# pe43711.net
KiCad netlist of a schematic drawn in EasyEDA Pro
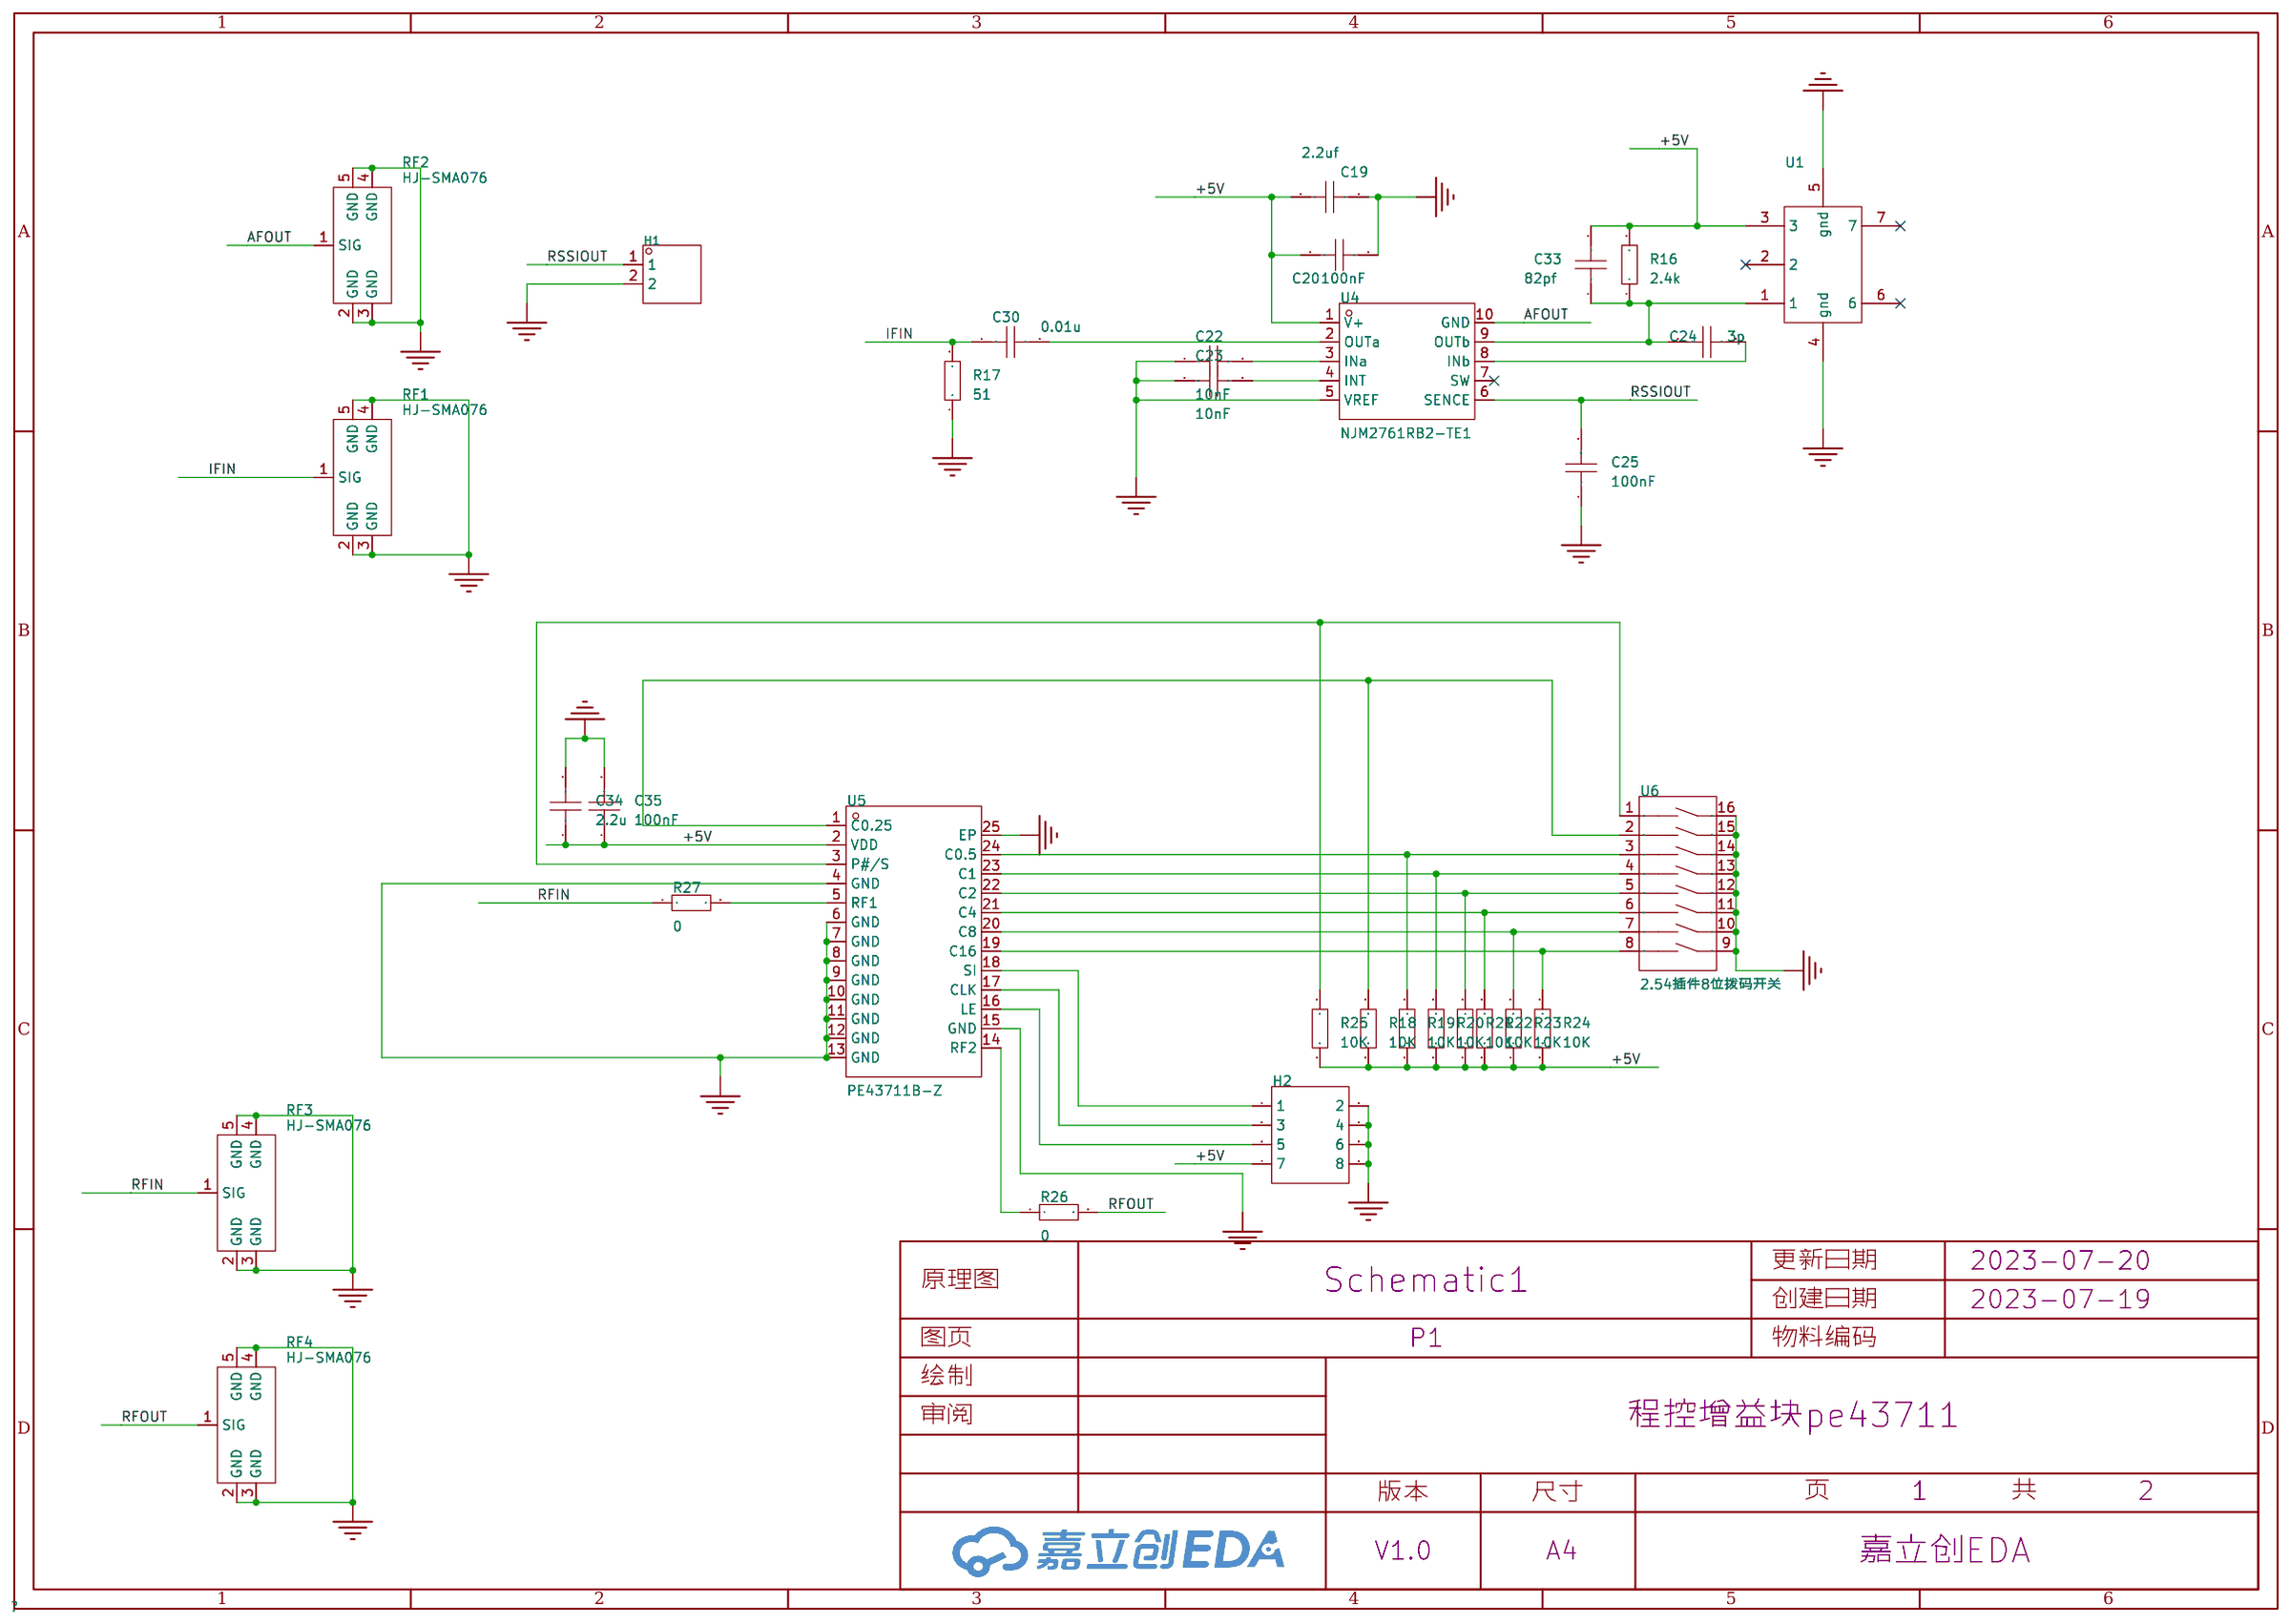
[diagram p0: P1]
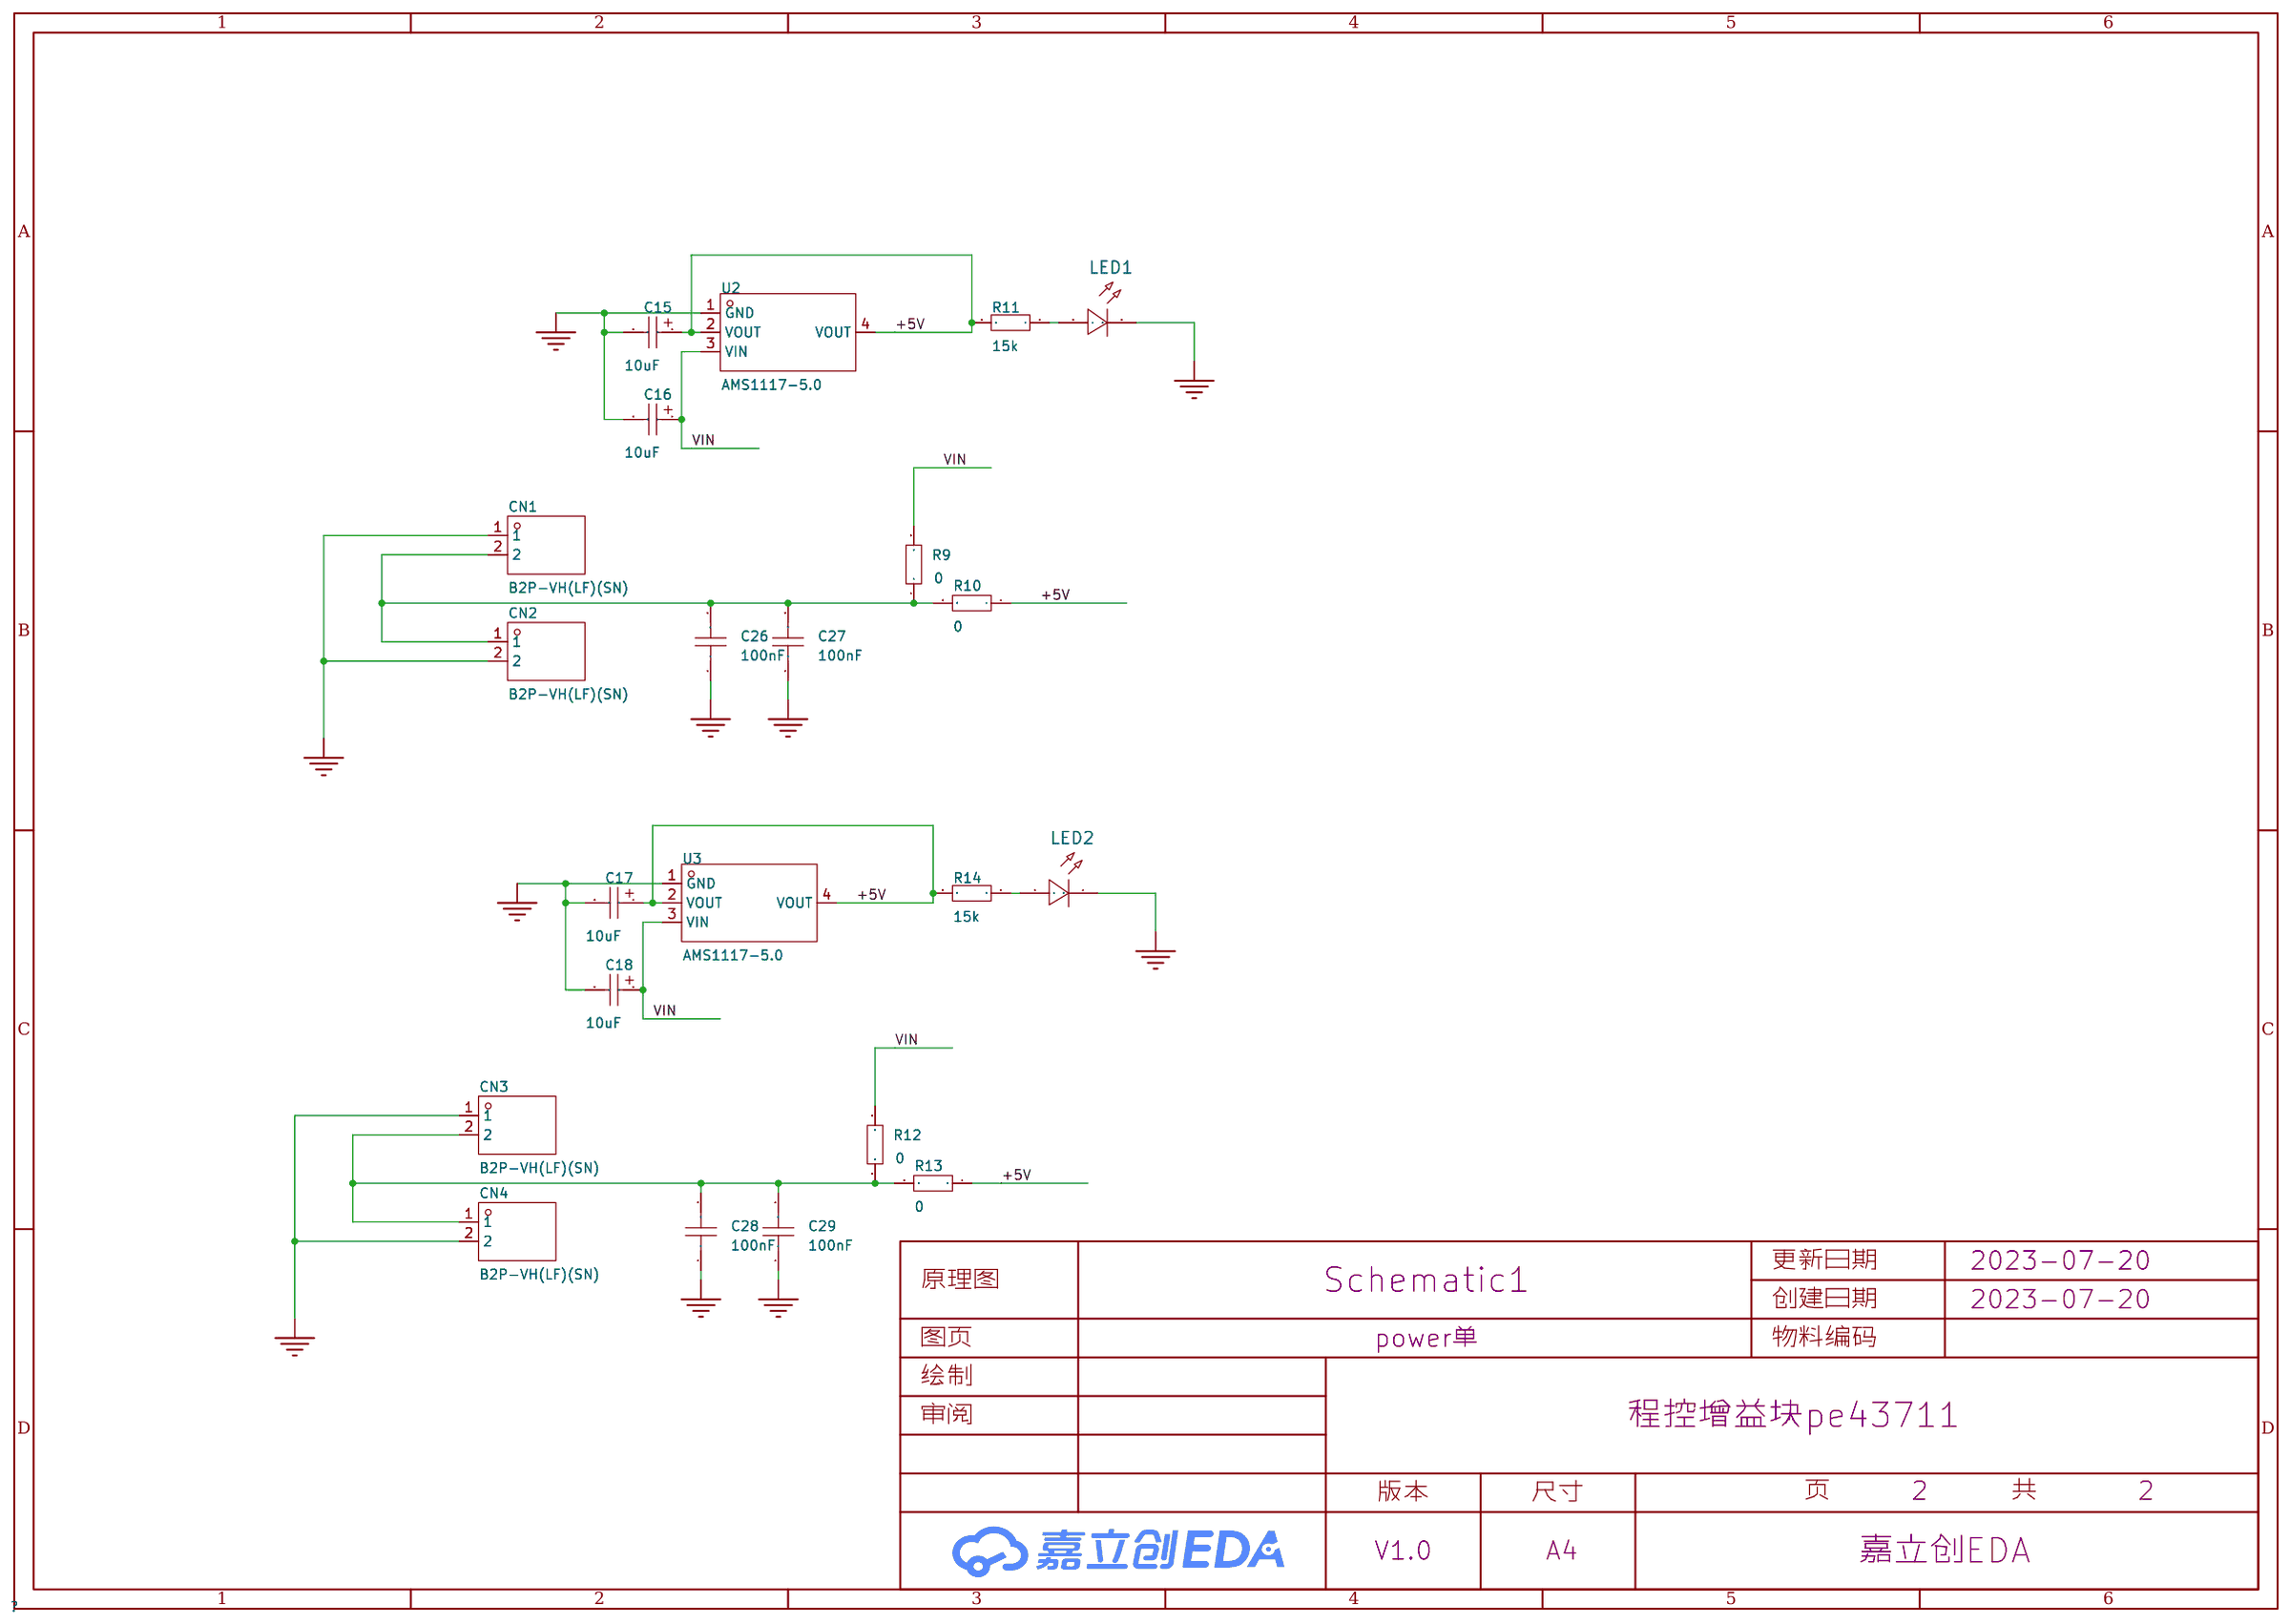
[diagram p1: power单]

(export (version "E")
  (design (tool "Eeschema 10.0.6"))
  (components
    (comp (ref "C19")
      (value "2.2uf")
      (footprint "easyedapro:C0603")
      (libsource (lib "easyedapro") (part "CapAcitance"))
    )
    (comp (ref "C20")
      (value "100nF")
      (footprint "easyedapro:C0603")
      (libsource (lib "easyedapro") (part "CapAcitance"))
    )
    (comp (ref "C22")
      (value "10nF")
      (footprint "easyedapro:C0603")
      (libsource (lib "easyedapro") (part "CapAcitance"))
    )
    (comp (ref "C23")
      (value "10nF")
      (footprint "easyedapro:C0603")
      (libsource (lib "easyedapro") (part "CapAcitance"))
    )
    (comp (ref "C24")
      (value "3p")
      (footprint "easyedapro:C0603")
      (libsource (lib "easyedapro") (part "CapAcitance"))
    )
    (comp (ref "C25")
      (value "100nF")
      (footprint "easyedapro:C0603")
      (libsource (lib "easyedapro") (part "CapAcitance"))
    )
    (comp (ref "C30")
      (value "0.01u")
      (footprint "easyedapro:C0603")
      (libsource (lib "easyedapro") (part "CapAcitance"))
    )
    (comp (ref "C33")
      (value "82pf")
      (footprint "easyedapro:C0603")
      (libsource (lib "easyedapro") (part "CapAcitance"))
    )
    (comp (ref "C34")
      (value "2.2u")
      (footprint "easyedapro:C0603")
      (libsource (lib "easyedapro") (part "CapAcitance"))
    )
    (comp (ref "C35")
      (value "100nF")
      (footprint "easyedapro:C0603")
      (libsource (lib "easyedapro") (part "CapAcitance"))
    )
    (comp (ref "H1")
      (value "~")
      (footprint "easyedapro:HDR-TH_2P-P2.54-V-M-1")
      (libsource (lib "easyedapro") (part "210S-1*2P L=11.6MMGold-plated black"))
    )
    (comp (ref "H2")
      (value "~")
      (footprint "easyedapro:HDR-TH_8P-P2.54-V-F-R2-C4-S2.54-1")
      (libsource (lib "easyedapro") (part "HDR-F-2.54_2x4"))
    )
    (comp (ref "R16")
      (value "2.4k")
      (footprint "easyedapro:R0603")
      (libsource (lib "easyedapro") (part "电阻"))
    )
    (comp (ref "R17") (value "51") (footprint "easyedapro:R0603") (libsource (lib "easyedapro") (part "电阻")))
    (comp (ref "R18") (value "10K") (footprint "easyedapro:R0603") (libsource (lib "easyedapro") (part "电阻")))
    (comp (ref "R19") (value "10K") (footprint "easyedapro:R0603") (libsource (lib "easyedapro") (part "电阻")))
    (comp (ref "R20") (value "10K") (footprint "easyedapro:R0603") (libsource (lib "easyedapro") (part "电阻")))
    (comp (ref "R21") (value "10K") (footprint "easyedapro:R0603") (libsource (lib "easyedapro") (part "电阻")))
    (comp (ref "R22") (value "10K") (footprint "easyedapro:R0603") (libsource (lib "easyedapro") (part "电阻")))
    (comp (ref "R23") (value "10K") (footprint "easyedapro:R0603") (libsource (lib "easyedapro") (part "电阻")))
    (comp (ref "R24") (value "10K") (footprint "easyedapro:R0603") (libsource (lib "easyedapro") (part "电阻")))
    (comp (ref "R25") (value "10K") (footprint "easyedapro:R0603") (libsource (lib "easyedapro") (part "电阻")))
    (comp (ref "R26") (value "0") (footprint "easyedapro:R0603") (libsource (lib "easyedapro") (part "电阻")))
    (comp (ref "R27") (value "0") (footprint "easyedapro:R0603") (libsource (lib "easyedapro") (part "电阻")))
    (comp (ref "RF1")
      (value "HJ-SMA076")
      (footprint "easyedapro:SMA-SMD_HJ-SMA076")
      (description "连接器类型:板端;射频系列:SMA;接口类型:内孔;端口数量:1;阻抗:-;频率-最大值:-;样式:偏脚;接口直径:-;接口长度/高度:-;工作温度范围:-;")
      (fields (field (name "Manufacturer") "皇捷"))
      (libsource (lib "easyedapro") (part "HJ-SMA076"))
    )
    (comp (ref "RF2")
      (value "HJ-SMA076")
      (footprint "easyedapro:SMA-SMD_HJ-SMA076")
      (description "连接器类型:板端;射频系列:SMA;接口类型:内孔;端口数量:1;阻抗:-;频率-最大值:-;样式:偏脚;接口直径:-;接口长度/高度:-;工作温度范围:-;")
      (fields (field (name "Manufacturer") "皇捷"))
      (libsource (lib "easyedapro") (part "HJ-SMA076"))
    )
    (comp (ref "RF3")
      (value "HJ-SMA076")
      (footprint "easyedapro:SMA-SMD_HJ-SMA076")
      (description "连接器类型:板端;射频系列:SMA;接口类型:内孔;端口数量:1;阻抗:-;频率-最大值:-;样式:偏脚;接口直径:-;接口长度/高度:-;工作温度范围:-;")
      (fields (field (name "Manufacturer") "皇捷"))
      (libsource (lib "easyedapro") (part "HJ-SMA076"))
    )
    (comp (ref "RF4")
      (value "HJ-SMA076")
      (footprint "easyedapro:SMA-SMD_HJ-SMA076")
      (description "连接器类型:板端;射频系列:SMA;接口类型:内孔;端口数量:1;阻抗:-;频率-最大值:-;样式:偏脚;接口直径:-;接口长度/高度:-;工作温度范围:-;")
      (fields (field (name "Manufacturer") "皇捷"))
      (libsource (lib "easyedapro") (part "HJ-SMA076"))
    )
    (comp (ref "U1") (value "~") (footprint "easyedapro:中周") (libsource (lib "easyedapro") (part "中周")))
    (comp (ref "U4")
      (value "NJM2761RB2-TE1")
      (footprint "easyedapro:MSOP-10_L2.9-W2.8-P0.50-LS4.0-BL")
      (fields (field (name "Manufacturer") "JRC"))
      (libsource (lib "easyedapro") (part "NJM2761RB2-TE1"))
    )
    (comp (ref "U5")
      (value "PE43711B-Z")
      (footprint "easyedapro:VQFN-24_L4.0-W4.0-P0.50-BL-EP2.3")
      (description "衰减值:0dB~31.75dB;频率范围:9kHz~6GHz;阻抗:50Ω;")
      (fields (field (name "Manufacturer") "PSemi"))
      (libsource (lib "easyedapro") (part "PE43711B-Z"))
    )
    (comp (ref "U6")
      (value "2.54插件8位拨码开关")
      (footprint "easyedapro:SW-TH_16P-L21.9-W9.9-P2.54-LS7.8")
      (libsource (lib "easyedapro") (part "2.54插件8位拨码开关"))
    )
    (comp (ref "C15")
      (value "10uF")
      (footprint "easyedapro:CAP-SMD_L3.2-W1.6-RD-C7171")
      (description "容值:10uF;精度:±10%;额定电压:16V;等效串联电阻:3Ω@100kHz;")
      (fields (field (name "Manufacturer Part") "TAJA106K016RNJ") (field (name "Manufacturer") "Kyocera AVX"))
      (libsource (lib "easyedapro") (part "TAJA106K016RNJ"))
    )
    (comp (ref "C16")
      (value "10uF")
      (footprint "easyedapro:CAP-SMD_L3.2-W1.6-RD-C7171")
      (description "容值:10uF;精度:±10%;额定电压:16V;等效串联电阻:3Ω@100kHz;")
      (fields (field (name "Manufacturer Part") "TAJA106K016RNJ") (field (name "Manufacturer") "Kyocera AVX"))
      (libsource (lib "easyedapro") (part "TAJA106K016RNJ"))
    )
    (comp (ref "C17")
      (value "10uF")
      (footprint "easyedapro:CAP-SMD_L3.2-W1.6-RD-C7171")
      (description "容值:10uF;精度:±10%;额定电压:16V;等效串联电阻:3Ω@100kHz;")
      (fields (field (name "Manufacturer Part") "TAJA106K016RNJ") (field (name "Manufacturer") "Kyocera AVX"))
      (libsource (lib "easyedapro") (part "TAJA106K016RNJ"))
    )
    (comp (ref "C18")
      (value "10uF")
      (footprint "easyedapro:CAP-SMD_L3.2-W1.6-RD-C7171")
      (description "容值:10uF;精度:±10%;额定电压:16V;等效串联电阻:3Ω@100kHz;")
      (fields (field (name "Manufacturer Part") "TAJA106K016RNJ") (field (name "Manufacturer") "Kyocera AVX"))
      (libsource (lib "easyedapro") (part "TAJA106K016RNJ"))
    )
    (comp (ref "C26")
      (value "100nF")
      (footprint "easyedapro:C0603")
      (libsource (lib "easyedapro") (part "CapAcitance"))
    )
    (comp (ref "C27")
      (value "100nF")
      (footprint "easyedapro:C0603")
      (libsource (lib "easyedapro") (part "CapAcitance"))
    )
    (comp (ref "C28")
      (value "100nF")
      (footprint "easyedapro:C0603")
      (libsource (lib "easyedapro") (part "CapAcitance"))
    )
    (comp (ref "C29")
      (value "100nF")
      (footprint "easyedapro:C0603")
      (libsource (lib "easyedapro") (part "CapAcitance"))
    )
    (comp (ref "CN1")
      (value "B2P-VH(LF)(SN)")
      (footprint "easyedapro:CONN-TH_B2P-VH-LF-SN")
      (description "参考系列:VH;间距:3.96mm;插针结构:1x2P;排数:1;每排PIN数:2;行距:-;安装方式:-;触头材质:黄铜;")
      (fields (field (name "Manufacturer") "JST"))
      (libsource (lib "easyedapro") (part "B2P-VH (LF)(SN)"))
    )
    (comp (ref "CN2")
      (value "B2P-VH(LF)(SN)")
      (footprint "easyedapro:CONN-TH_B2P-VH-LF-SN")
      (description "参考系列:VH;间距:3.96mm;插针结构:1x2P;排数:1;每排PIN数:2;行距:-;安装方式:-;触头材质:黄铜;")
      (fields (field (name "Manufacturer") "JST"))
      (libsource (lib "easyedapro") (part "B2P-VH (LF)(SN)"))
    )
    (comp (ref "CN3")
      (value "B2P-VH(LF)(SN)")
      (footprint "easyedapro:CONN-TH_B2P-VH-LF-SN")
      (description "参考系列:VH;间距:3.96mm;插针结构:1x2P;排数:1;每排PIN数:2;行距:-;安装方式:-;触头材质:黄铜;")
      (fields (field (name "Manufacturer") "JST"))
      (libsource (lib "easyedapro") (part "B2P-VH (LF)(SN)"))
    )
    (comp (ref "CN4")
      (value "B2P-VH(LF)(SN)")
      (footprint "easyedapro:CONN-TH_B2P-VH-LF-SN")
      (description "参考系列:VH;间距:3.96mm;插针结构:1x2P;排数:1;每排PIN数:2;行距:-;安装方式:-;触头材质:黄铜;")
      (fields (field (name "Manufacturer") "JST"))
      (libsource (lib "easyedapro") (part "B2P-VH (LF)(SN)"))
    )
    (comp (ref "LED1")
      (value "~")
      (footprint "easyedapro:LED_0603")
      (libsource (lib "easyedapro") (part "LED_R"))
    )
    (comp (ref "LED2")
      (value "~")
      (footprint "easyedapro:LED_0603")
      (libsource (lib "easyedapro") (part "LED_R"))
    )
    (comp (ref "R9") (value "0") (footprint "easyedapro:R0603") (libsource (lib "easyedapro") (part "电阻")))
    (comp (ref "R10") (value "0") (footprint "easyedapro:R0603") (libsource (lib "easyedapro") (part "电阻")))
    (comp (ref "R11") (value "15k") (footprint "easyedapro:R0603") (libsource (lib "easyedapro") (part "电阻")))
    (comp (ref "R12") (value "0") (footprint "easyedapro:R0603") (libsource (lib "easyedapro") (part "电阻")))
    (comp (ref "R13") (value "0") (footprint "easyedapro:R0603") (libsource (lib "easyedapro") (part "电阻")))
    (comp (ref "R14") (value "15k") (footprint "easyedapro:R0603") (libsource (lib "easyedapro") (part "电阻")))
    (comp (ref "U2")
      (value "AMS1117-5.0")
      (footprint "easyedapro:SOT-223_L6.5-W3.5-P2.30-LS7.0-BR")
      (description "输出类型:固定;输出极性:正;最大输入电压:15V;输出电压:5V;输出电流:1A;电源纹波抑制比(PSRR):68dB@(120Hz);")
      (fields (field (name "Manufacturer") "AMS"))
      (libsource (lib "easyedapro") (part "AMS1117-5.0"))
    )
    (comp (ref "U3")
      (value "AMS1117-5.0")
      (footprint "easyedapro:SOT-223_L6.5-W3.5-P2.30-LS7.0-BR")
      (description "输出类型:固定;输出极性:正;最大输入电压:15V;输出电压:5V;输出电流:1A;电源纹波抑制比(PSRR):68dB@(120Hz);")
      (fields (field (name "Manufacturer") "AMS"))
      (libsource (lib "easyedapro") (part "AMS1117-5.0"))
    )
  )
  (nets
    (net (code "1") (name "+5V") (class "Default")
      (node (ref "C15") (pin "1") (pinfunction "1_1") (pintype "input"))
      (node (ref "C17") (pin "1") (pinfunction "1_1") (pintype "input"))
      (node (ref "C19") (pin "1") (pinfunction "1_1") (pintype "input"))
      (node (ref "C20") (pin "1") (pinfunction "1_1") (pintype "input"))
      (node (ref "C33") (pin "2") (pinfunction "2_2") (pintype "input"))
      (node (ref "C34") (pin "1") (pinfunction "1_1") (pintype "input"))
      (node (ref "C35") (pin "1") (pinfunction "1_1") (pintype "input"))
      (node (ref "H2") (pin "7") (pinfunction "7_7") (pintype "input"))
      (node (ref "R10") (pin "1") (pinfunction "1_1") (pintype "input"))
      (node (ref "R11") (pin "2") (pinfunction "2_2") (pintype "input"))
      (node (ref "R13") (pin "1") (pinfunction "1_1") (pintype "input"))
      (node (ref "R14") (pin "2") (pinfunction "2_2") (pintype "input"))
      (node (ref "R16") (pin "2") (pinfunction "2_2") (pintype "input"))
      (node (ref "R18") (pin "1") (pinfunction "1_1") (pintype "input"))
      (node (ref "R19") (pin "1") (pinfunction "1_1") (pintype "input"))
      (node (ref "R20") (pin "1") (pinfunction "1_1") (pintype "input"))
      (node (ref "R21") (pin "1") (pinfunction "1_1") (pintype "input"))
      (node (ref "R22") (pin "1") (pinfunction "1_1") (pintype "input"))
      (node (ref "R23") (pin "1") (pinfunction "1_1") (pintype "input"))
      (node (ref "R24") (pin "1") (pinfunction "1_1") (pintype "input"))
      (node (ref "R25") (pin "1") (pinfunction "1_1") (pintype "input"))
      (node (ref "U1") (pin "3") (pinfunction "3_3") (pintype "input"))
      (node (ref "U2") (pin "2") (pinfunction "VOUT_2") (pintype "input"))
      (node (ref "U2") (pin "4") (pinfunction "VOUT_4") (pintype "input"))
      (node (ref "U3") (pin "2") (pinfunction "VOUT_2") (pintype "input"))
      (node (ref "U3") (pin "4") (pinfunction "VOUT_4") (pintype "input"))
      (node (ref "U4") (pin "1") (pinfunction "V+_1") (pintype "input"))
      (node (ref "U5") (pin "2") (pinfunction "VDD_2") (pintype "input"))
    )
    (net (code "2") (name "AFOUT") (class "Default")
      (node (ref "RF2") (pin "1") (pinfunction "SIG_1") (pintype "input"))
      (node (ref "U4") (pin "10") (pinfunction "GND_10") (pintype "input"))
    )
    (net (code "3") (name "GND") (class "Default")
      (node (ref "C15") (pin "2") (pinfunction "2_2") (pintype "input"))
      (node (ref "C16") (pin "2") (pinfunction "2_2") (pintype "input"))
      (node (ref "C17") (pin "2") (pinfunction "2_2") (pintype "input"))
      (node (ref "C18") (pin "2") (pinfunction "2_2") (pintype "input"))
      (node (ref "C19") (pin "2") (pinfunction "2_2") (pintype "input"))
      (node (ref "C20") (pin "2") (pinfunction "2_2") (pintype "input"))
      (node (ref "C22") (pin "1") (pinfunction "1_1") (pintype "input"))
      (node (ref "C23") (pin "1") (pinfunction "1_1") (pintype "input"))
      (node (ref "C25") (pin "1") (pinfunction "1_1") (pintype "input"))
      (node (ref "C26") (pin "1") (pinfunction "1_1") (pintype "input"))
      (node (ref "C27") (pin "1") (pinfunction "1_1") (pintype "input"))
      (node (ref "C28") (pin "1") (pinfunction "1_1") (pintype "input"))
      (node (ref "C29") (pin "1") (pinfunction "1_1") (pintype "input"))
      (node (ref "C34") (pin "2") (pinfunction "2_2") (pintype "input"))
      (node (ref "C35") (pin "2") (pinfunction "2_2") (pintype "input"))
      (node (ref "CN1") (pin "1") (pinfunction "1_1") (pintype "input"))
      (node (ref "CN2") (pin "2") (pinfunction "2_2") (pintype "input"))
      (node (ref "CN3") (pin "1") (pinfunction "1_1") (pintype "input"))
      (node (ref "CN4") (pin "2") (pinfunction "2_2") (pintype "input"))
      (node (ref "H1") (pin "2") (pinfunction "2_2") (pintype "input"))
      (node (ref "H2") (pin "2") (pinfunction "2_2") (pintype "input"))
      (node (ref "H2") (pin "4") (pinfunction "4_4") (pintype "input"))
      (node (ref "H2") (pin "6") (pinfunction "6_6") (pintype "input"))
      (node (ref "H2") (pin "8") (pinfunction "8_8") (pintype "input"))
      (node (ref "LED1") (pin "1") (pinfunction "C_1") (pintype "input"))
      (node (ref "LED2") (pin "1") (pinfunction "C_1") (pintype "input"))
      (node (ref "R17") (pin "1") (pinfunction "1_1") (pintype "input"))
      (node (ref "RF1") (pin "2") (pinfunction "GND_2") (pintype "input"))
      (node (ref "RF1") (pin "3") (pinfunction "GND_3") (pintype "input"))
      (node (ref "RF1") (pin "4") (pinfunction "GND_4") (pintype "input"))
      (node (ref "RF1") (pin "5") (pinfunction "GND_5") (pintype "input"))
      (node (ref "RF2") (pin "2") (pinfunction "GND_2") (pintype "input"))
      (node (ref "RF2") (pin "3") (pinfunction "GND_3") (pintype "input"))
      (node (ref "RF2") (pin "4") (pinfunction "GND_4") (pintype "input"))
      (node (ref "RF2") (pin "5") (pinfunction "GND_5") (pintype "input"))
      (node (ref "RF3") (pin "2") (pinfunction "GND_2") (pintype "input"))
      (node (ref "RF3") (pin "3") (pinfunction "GND_3") (pintype "input"))
      (node (ref "RF3") (pin "4") (pinfunction "GND_4") (pintype "input"))
      (node (ref "RF3") (pin "5") (pinfunction "GND_5") (pintype "input"))
      (node (ref "RF4") (pin "2") (pinfunction "GND_2") (pintype "input"))
      (node (ref "RF4") (pin "3") (pinfunction "GND_3") (pintype "input"))
      (node (ref "RF4") (pin "4") (pinfunction "GND_4") (pintype "input"))
      (node (ref "RF4") (pin "5") (pinfunction "GND_5") (pintype "input"))
      (node (ref "U1") (pin "4") (pinfunction "gnd_4") (pintype "input"))
      (node (ref "U1") (pin "5") (pinfunction "gnd_5") (pintype "input"))
      (node (ref "U2") (pin "1") (pinfunction "GND_1") (pintype "input"))
      (node (ref "U3") (pin "1") (pinfunction "GND_1") (pintype "input"))
      (node (ref "U4") (pin "5") (pinfunction "VREF_5") (pintype "input"))
      (node (ref "U5") (pin "10") (pinfunction "GND_10") (pintype "input"))
      (node (ref "U5") (pin "11") (pinfunction "GND_11") (pintype "input"))
      (node (ref "U5") (pin "12") (pinfunction "GND_12") (pintype "input"))
      (node (ref "U5") (pin "13") (pinfunction "GND_13") (pintype "input"))
      (node (ref "U5") (pin "15") (pinfunction "GND_15") (pintype "input"))
      (node (ref "U5") (pin "25") (pinfunction "EP_25") (pintype "input"))
      (node (ref "U5") (pin "4") (pinfunction "GND_4") (pintype "input"))
      (node (ref "U5") (pin "6") (pinfunction "GND_6") (pintype "input"))
      (node (ref "U5") (pin "7") (pinfunction "GND_7") (pintype "input"))
      (node (ref "U5") (pin "8") (pinfunction "GND_8") (pintype "input"))
      (node (ref "U5") (pin "9") (pinfunction "GND_9") (pintype "input"))
      (node (ref "U6") (pin "10") (pinfunction "10_10") (pintype "input"))
      (node (ref "U6") (pin "11") (pinfunction "11_11") (pintype "input"))
      (node (ref "U6") (pin "12") (pinfunction "12_12") (pintype "input"))
      (node (ref "U6") (pin "13") (pinfunction "13_13") (pintype "input"))
      (node (ref "U6") (pin "14") (pinfunction "14_14") (pintype "input"))
      (node (ref "U6") (pin "15") (pinfunction "15_15") (pintype "input"))
      (node (ref "U6") (pin "16") (pinfunction "16_16") (pintype "input"))
      (node (ref "U6") (pin "9") (pinfunction "9_9") (pintype "input"))
    )
    (net (code "4") (name "IFIN") (class "Default")
      (node (ref "C30") (pin "1") (pinfunction "1_1") (pintype "input"))
      (node (ref "R17") (pin "2") (pinfunction "2_2") (pintype "input"))
      (node (ref "RF1") (pin "1") (pinfunction "SIG_1") (pintype "input"))
    )
    (net (code "5") (name "Net-(C26-Pad2)") (class "Default")
      (node (ref "C26") (pin "2") (pinfunction "2_2") (pintype "input"))
      (node (ref "C27") (pin "2") (pinfunction "2_2") (pintype "input"))
      (node (ref "CN1") (pin "2") (pinfunction "2_2") (pintype "input"))
      (node (ref "CN2") (pin "1") (pinfunction "1_1") (pintype "input"))
      (node (ref "R10") (pin "2") (pinfunction "2_2") (pintype "input"))
      (node (ref "R9") (pin "1") (pinfunction "1_1") (pintype "input"))
    )
    (net (code "6") (name "Net-(C28-Pad2)") (class "Default")
      (node (ref "C28") (pin "2") (pinfunction "2_2") (pintype "input"))
      (node (ref "C29") (pin "2") (pinfunction "2_2") (pintype "input"))
      (node (ref "CN3") (pin "2") (pinfunction "2_2") (pintype "input"))
      (node (ref "CN4") (pin "1") (pinfunction "1_1") (pintype "input"))
      (node (ref "R12") (pin "1") (pinfunction "1_1") (pintype "input"))
      (node (ref "R13") (pin "2") (pinfunction "2_2") (pintype "input"))
    )
    (net (code "7") (name "Net-(LED1-A)") (class "Default")
      (node (ref "LED1") (pin "2") (pinfunction "A_2") (pintype "input"))
      (node (ref "R11") (pin "1") (pinfunction "1_1") (pintype "input"))
    )
    (net (code "8") (name "Net-(LED2-A)") (class "Default")
      (node (ref "LED2") (pin "2") (pinfunction "A_2") (pintype "input"))
      (node (ref "R14") (pin "1") (pinfunction "1_1") (pintype "input"))
    )
    (net (code "9") (name "Net-(U4-INT)") (class "Default")
      (node (ref "C23") (pin "2") (pinfunction "2_2") (pintype "input"))
      (node (ref "U4") (pin "4") (pinfunction "INT_4") (pintype "input"))
    )
    (net (code "10") (name "Net-(U4-INa)") (class "Default")
      (node (ref "C22") (pin "2") (pinfunction "2_2") (pintype "input"))
      (node (ref "U4") (pin "3") (pinfunction "INa_3") (pintype "input"))
    )
    (net (code "11") (name "Net-(U4-INb)") (class "Default")
      (node (ref "C24") (pin "2") (pinfunction "2_2") (pintype "input"))
      (node (ref "U4") (pin "8") (pinfunction "INb_8") (pintype "input"))
    )
    (net (code "12") (name "Net-(U4-OUTa)") (class "Default")
      (node (ref "C30") (pin "2") (pinfunction "2_2") (pintype "input"))
      (node (ref "U4") (pin "2") (pinfunction "OUTa_2") (pintype "input"))
    )
    (net (code "13") (name "Net-(U4-OUTb)") (class "Default")
      (node (ref "C24") (pin "1") (pinfunction "1_1") (pintype "input"))
      (node (ref "C33") (pin "1") (pinfunction "1_1") (pintype "input"))
      (node (ref "R16") (pin "1") (pinfunction "1_1") (pintype "input"))
      (node (ref "U1") (pin "1") (pinfunction "1_1") (pintype "input"))
      (node (ref "U4") (pin "9") (pinfunction "OUTb_9") (pintype "input"))
    )
    (net (code "14") (name "Net-(U5-C0.5)") (class "Default")
      (node (ref "R19") (pin "2") (pinfunction "2_2") (pintype "input"))
      (node (ref "U5") (pin "24") (pinfunction "C0.5_24") (pintype "input"))
      (node (ref "U6") (pin "3") (pinfunction "3_3") (pintype "input"))
    )
    (net (code "15") (name "Net-(U5-C0.25)") (class "Default")
      (node (ref "R18") (pin "2") (pinfunction "2_2") (pintype "input"))
      (node (ref "U5") (pin "1") (pinfunction "C0.25_1") (pintype "input"))
      (node (ref "U6") (pin "2") (pinfunction "2_2") (pintype "input"))
    )
    (net (code "16") (name "Net-(U5-C1)") (class "Default")
      (node (ref "R20") (pin "2") (pinfunction "2_2") (pintype "input"))
      (node (ref "U5") (pin "23") (pinfunction "C1_23") (pintype "input"))
      (node (ref "U6") (pin "4") (pinfunction "4_4") (pintype "input"))
    )
    (net (code "17") (name "Net-(U5-C2)") (class "Default")
      (node (ref "R21") (pin "2") (pinfunction "2_2") (pintype "input"))
      (node (ref "U5") (pin "22") (pinfunction "C2_22") (pintype "input"))
      (node (ref "U6") (pin "5") (pinfunction "5_5") (pintype "input"))
    )
    (net (code "18") (name "Net-(U5-C4)") (class "Default")
      (node (ref "R22") (pin "2") (pinfunction "2_2") (pintype "input"))
      (node (ref "U5") (pin "21") (pinfunction "C4_21") (pintype "input"))
      (node (ref "U6") (pin "6") (pinfunction "6_6") (pintype "input"))
    )
    (net (code "19") (name "Net-(U5-C8)") (class "Default")
      (node (ref "R23") (pin "2") (pinfunction "2_2") (pintype "input"))
      (node (ref "U5") (pin "20") (pinfunction "C8_20") (pintype "input"))
      (node (ref "U6") (pin "7") (pinfunction "7_7") (pintype "input"))
    )
    (net (code "20") (name "Net-(U5-C16)") (class "Default")
      (node (ref "R24") (pin "2") (pinfunction "2_2") (pintype "input"))
      (node (ref "U5") (pin "19") (pinfunction "C16_19") (pintype "input"))
      (node (ref "U6") (pin "8") (pinfunction "8_8") (pintype "input"))
    )
    (net (code "21") (name "Net-(U5-CLK)") (class "Default")
      (node (ref "H2") (pin "3") (pinfunction "3_3") (pintype "input"))
      (node (ref "U5") (pin "17") (pinfunction "CLK_17") (pintype "input"))
    )
    (net (code "22") (name "Net-(U5-LE)") (class "Default")
      (node (ref "H2") (pin "5") (pinfunction "5_5") (pintype "input"))
      (node (ref "U5") (pin "16") (pinfunction "LE_16") (pintype "input"))
    )
    (net (code "23") (name "Net-(U5-P#{slash}S)") (class "Default")
      (node (ref "R25") (pin "2") (pinfunction "2_2") (pintype "input"))
      (node (ref "U5") (pin "3") (pinfunction "P#/S_3") (pintype "input"))
      (node (ref "U6") (pin "1") (pinfunction "1_1") (pintype "input"))
    )
    (net (code "24") (name "Net-(U5-RF1)") (class "Default")
      (node (ref "R27") (pin "2") (pinfunction "2_2") (pintype "input"))
      (node (ref "U5") (pin "5") (pinfunction "RF1_5") (pintype "input"))
    )
    (net (code "25") (name "Net-(U5-RF2)") (class "Default")
      (node (ref "R26") (pin "1") (pinfunction "1_1") (pintype "input"))
      (node (ref "U5") (pin "14") (pinfunction "RF2_14") (pintype "input"))
    )
    (net (code "26") (name "Net-(U5-SI)") (class "Default")
      (node (ref "H2") (pin "1") (pinfunction "1_1") (pintype "input"))
      (node (ref "U5") (pin "18") (pinfunction "SI_18") (pintype "input"))
    )
    (net (code "27") (name "RFIN") (class "Default")
      (node (ref "R27") (pin "1") (pinfunction "1_1") (pintype "input"))
      (node (ref "RF3") (pin "1") (pinfunction "SIG_1") (pintype "input"))
    )
    (net (code "28") (name "RFOUT") (class "Default")
      (node (ref "R26") (pin "2") (pinfunction "2_2") (pintype "input"))
      (node (ref "RF4") (pin "1") (pinfunction "SIG_1") (pintype "input"))
    )
    (net (code "29") (name "RSSIOUT") (class "Default")
      (node (ref "C25") (pin "2") (pinfunction "2_2") (pintype "input"))
      (node (ref "H1") (pin "1") (pinfunction "1_1") (pintype "input"))
      (node (ref "U4") (pin "6") (pinfunction "SENCE_6") (pintype "input"))
    )
    (net (code "30") (name "VIN") (class "Default")
      (node (ref "C16") (pin "1") (pinfunction "1_1") (pintype "input"))
      (node (ref "C18") (pin "1") (pinfunction "1_1") (pintype "input"))
      (node (ref "R12") (pin "2") (pinfunction "2_2") (pintype "input"))
      (node (ref "R9") (pin "2") (pinfunction "2_2") (pintype "input"))
      (node (ref "U2") (pin "3") (pinfunction "VIN_3") (pintype "input"))
      (node (ref "U3") (pin "3") (pinfunction "VIN_3") (pintype "input"))
    )
    (net (code "31") (name "unconnected-(U1-Pad2)") (class "Default")
      (node (ref "U1") (pin "2") (pinfunction "2_2") (pintype "input+no_connect"))
    )
    (net (code "32") (name "unconnected-(U1-Pad6)") (class "Default")
      (node (ref "U1") (pin "6") (pinfunction "6_6") (pintype "input+no_connect"))
    )
    (net (code "33") (name "unconnected-(U1-Pad7)") (class "Default")
      (node (ref "U1") (pin "7") (pinfunction "7_7") (pintype "input+no_connect"))
    )
    (net (code "34") (name "unconnected-(U4-SW-Pad7)") (class "Default")
      (node (ref "U4") (pin "7") (pinfunction "SW_7") (pintype "input+no_connect"))
    )
  )
)
